# art_limb.net
KiCad netlist of a schematic drawn in EAGLE
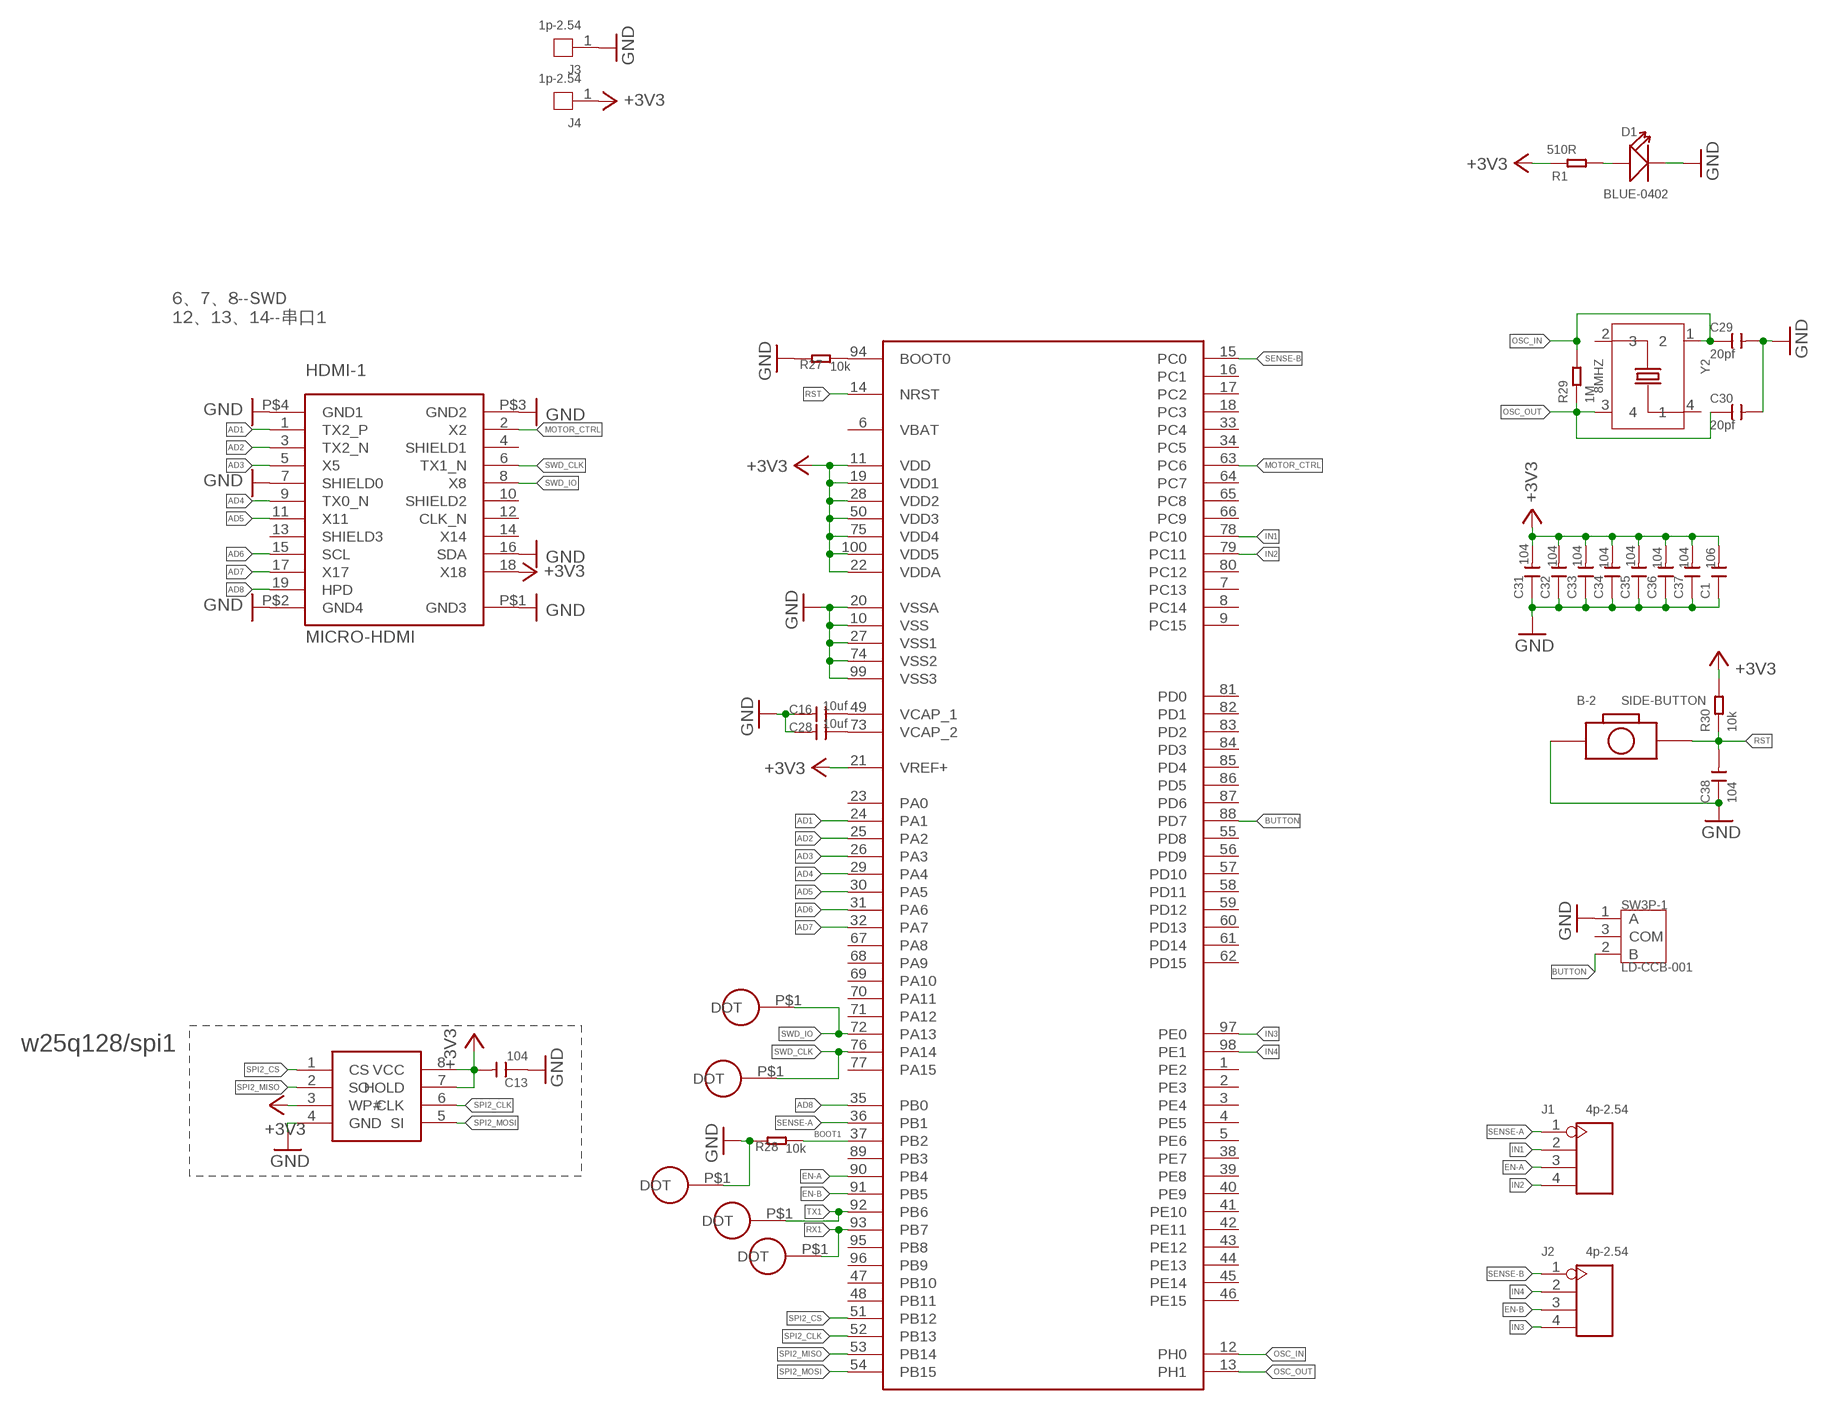
[diagram p0: schematic, sheet 1]

(export (version "E")
  (design (tool "Eeschema 10.0.6"))
  (components
    (comp (ref "B-2")
      (value "SIDE-BUTTON")
      (footprint "eagle-import:SIDE-BUTTON")
      (libsource (lib "eagle-import") (part "SIDE-BUTTON"))
    )
    (comp (ref "C1")
      (value "106")
      (footprint "eagle-import:C0402")
      (fields (field (name "MPN") "GRM1555C1H150JA01D"))
      (libsource (lib "eagle-import") (part "CAP-(0402)"))
    )
    (comp (ref "C13")
      (value "104")
      (footprint "eagle-import:C0402")
      (fields (field (name "MPN") "GRM1555C1H150JA01D"))
      (libsource (lib "eagle-import") (part "CAP-(0402)"))
    )
    (comp (ref "C16")
      (value "10uf")
      (footprint "eagle-import:C0402")
      (fields (field (name "MPN") "GRM1555C1H150JA01D"))
      (libsource (lib "eagle-import") (part "CAP-(0402)"))
    )
    (comp (ref "C28")
      (value "10uf")
      (footprint "eagle-import:C0402")
      (fields (field (name "MPN") "GRM1555C1H150JA01D"))
      (libsource (lib "eagle-import") (part "CAP-(0402)"))
    )
    (comp (ref "C29")
      (value "20pf")
      (footprint "eagle-import:C0402")
      (fields (field (name "MPN") "GRM1555C1H150JA01D"))
      (libsource (lib "eagle-import") (part "CAP-(0402)"))
    )
    (comp (ref "C30")
      (value "20pf")
      (footprint "eagle-import:C0402")
      (fields (field (name "MPN") "GRM1555C1H150JA01D"))
      (libsource (lib "eagle-import") (part "CAP-(0402)"))
    )
    (comp (ref "C31")
      (value "104")
      (footprint "eagle-import:C0402")
      (fields (field (name "MPN") "GRM1555C1H150JA01D"))
      (libsource (lib "eagle-import") (part "CAP-(0402)"))
    )
    (comp (ref "C32")
      (value "104")
      (footprint "eagle-import:C0402")
      (fields (field (name "MPN") "GRM1555C1H150JA01D"))
      (libsource (lib "eagle-import") (part "CAP-(0402)"))
    )
    (comp (ref "C33")
      (value "104")
      (footprint "eagle-import:C0402")
      (fields (field (name "MPN") "GRM1555C1H150JA01D"))
      (libsource (lib "eagle-import") (part "CAP-(0402)"))
    )
    (comp (ref "C34")
      (value "104")
      (footprint "eagle-import:C0402")
      (fields (field (name "MPN") "GRM1555C1H150JA01D"))
      (libsource (lib "eagle-import") (part "CAP-(0402)"))
    )
    (comp (ref "C35")
      (value "104")
      (footprint "eagle-import:C0402")
      (fields (field (name "MPN") "GRM1555C1H150JA01D"))
      (libsource (lib "eagle-import") (part "CAP-(0402)"))
    )
    (comp (ref "C36")
      (value "104")
      (footprint "eagle-import:C0402")
      (fields (field (name "MPN") "GRM1555C1H150JA01D"))
      (libsource (lib "eagle-import") (part "CAP-(0402)"))
    )
    (comp (ref "C37")
      (value "104")
      (footprint "eagle-import:C0402")
      (fields (field (name "MPN") "GRM1555C1H150JA01D"))
      (libsource (lib "eagle-import") (part "CAP-(0402)"))
    )
    (comp (ref "C38")
      (value "104")
      (footprint "eagle-import:C0402")
      (fields (field (name "MPN") "GRM1555C1H150JA01D"))
      (libsource (lib "eagle-import") (part "CAP-(0402)"))
    )
    (comp (ref "D1")
      (value "BLUE-0402")
      (footprint "eagle-import:LED-0402")
      (fields (field (name "MPN") "BL-HB337A-AV-TRB"))
      (libsource (lib "eagle-import") (part "LED-(0402)"))
    )
    (comp (ref "HDMI-1")
      (value "MICRO-HDMI")
      (footprint "eagle-import:HDMI")
      (libsource (lib "eagle-import") (part "MICRO-HDMI"))
    )
    (comp (ref "J1")
      (value "4p-2.54")
      (footprint "eagle-import:H4-2.54")
      (fields (field (name "MPN") "F185-1104A1BSYA1"))
      (libsource (lib "eagle-import") (part "DIP-BLACK-FEMALE-HEADER-VERT(4P-2.54)"))
    )
    (comp (ref "J2")
      (value "4p-2.54")
      (footprint "eagle-import:H4-2.54")
      (fields (field (name "MPN") "F185-1104A1BSYA1"))
      (libsource (lib "eagle-import") (part "DIP-BLACK-FEMALE-HEADER-VERT(4P-2.54)"))
    )
    (comp (ref "J3")
      (value "1p-2.54")
      (footprint "eagle-import:1P-65_35MIL")
      (fields (field (name "MPN") "RF130-1013BBS0741"))
      (libsource (lib "eagle-import") (part "DIP-BLACK-ROUND-FEMALE-HEADER-VERT(1P-2.54)"))
    )
    (comp (ref "J4")
      (value "1p-2.54")
      (footprint "eagle-import:1P-65_35MIL")
      (fields (field (name "MPN") "RF130-1013BBS0741"))
      (libsource (lib "eagle-import") (part "DIP-BLACK-ROUND-FEMALE-HEADER-VERT(1P-2.54)"))
    )
    (comp (ref "R1")
      (value "510R")
      (footprint "eagle-import:R0402")
      (fields (field (name "MPN") "RC0402JR-070RL"))
      (libsource (lib "eagle-import") (part "RES-(0402)"))
    )
    (comp (ref "R27")
      (value "10k")
      (footprint "eagle-import:R0402")
      (fields (field (name "MPN") "RC0402JR-070RL"))
      (libsource (lib "eagle-import") (part "RES-(0402)"))
    )
    (comp (ref "R28")
      (value "10k")
      (footprint "eagle-import:R0402")
      (fields (field (name "MPN") "RC0402JR-070RL"))
      (libsource (lib "eagle-import") (part "RES-(0402)"))
    )
    (comp (ref "R29")
      (value "1M")
      (footprint "eagle-import:R0402")
      (fields (field (name "MPN") "RC0402JR-070RL"))
      (libsource (lib "eagle-import") (part "RES-(0402)"))
    )
    (comp (ref "R30")
      (value "10k")
      (footprint "eagle-import:R0402")
      (fields (field (name "MPN") "RC0402JR-070RL"))
      (libsource (lib "eagle-import") (part "RES-(0402)"))
    )
    (comp (ref "SW3P-1")
      (value "LD-CCB-001")
      (footprint "eagle-import:SW3-2.54-9.0X3.5X3.5+2.0MM")
      (libsource (lib "eagle-import") (part "SWITCH(3P)"))
    )
    (comp (ref "U$1")
      (value "STM32F40XSTM32D40X")
      (footprint "eagle-import:LQFP100")
      (libsource (lib "eagle-import") (part "STM32F40XSTM32D40X"))
    )
    (comp (ref "U$2")
      (value "TEST-POINT")
      (footprint "eagle-import:TEST-POINT")
      (libsource (lib "eagle-import") (part "TEST-POINT"))
    )
    (comp (ref "U$3")
      (value "TEST-POINT")
      (footprint "eagle-import:TEST-POINT")
      (libsource (lib "eagle-import") (part "TEST-POINT"))
    )
    (comp (ref "U$4")
      (value "TEST-POINT")
      (footprint "eagle-import:TEST-POINT")
      (libsource (lib "eagle-import") (part "TEST-POINT"))
    )
    (comp (ref "U$5")
      (value "TEST-POINT")
      (footprint "eagle-import:TEST-POINT")
      (libsource (lib "eagle-import") (part "TEST-POINT"))
    )
    (comp (ref "U$6")
      (value "TEST-POINT")
      (footprint "eagle-import:TEST-POINT")
      (libsource (lib "eagle-import") (part "TEST-POINT"))
    )
    (comp (ref "W25Q128")
      (value "W25Q128")
      (footprint "eagle-import:SOP08")
      (libsource (lib "eagle-import") (part "W25Q128"))
    )
    (comp (ref "Y2")
      (value "8MHZ")
      (footprint "eagle-import:X4-SMD-3.2X2.5X0.7MM")
      (fields (field (name "MPN") "7M-27.120MAAJ-T"))
      (libsource (lib "eagle-import") (part "SMD-CRYSTAL-27.12MHZ-18PF-30PPM-60R(4P-3.2X2.5MM)"))
    )
  )
  (nets
    (net (code "1") (name "+3V3") (class "Default")
      (node (ref "C1") (pin "2") (pinfunction "2_2") (pintype "passive"))
      (node (ref "C13") (pin "2") (pinfunction "2_2") (pintype "passive"))
      (node (ref "C31") (pin "2") (pinfunction "2_2") (pintype "passive"))
      (node (ref "C32") (pin "2") (pinfunction "2_2") (pintype "passive"))
      (node (ref "C33") (pin "2") (pinfunction "2_2") (pintype "passive"))
      (node (ref "C34") (pin "2") (pinfunction "2_2") (pintype "passive"))
      (node (ref "C35") (pin "2") (pinfunction "2_2") (pintype "passive"))
      (node (ref "C36") (pin "2") (pinfunction "2_2") (pintype "passive"))
      (node (ref "C37") (pin "2") (pinfunction "2_2") (pintype "passive"))
      (node (ref "HDMI-1") (pin "18") (pinfunction "X18_18") (pintype "bidirectional"))
      (node (ref "J4") (pin "1") (pinfunction "1_1") (pintype "bidirectional"))
      (node (ref "R1") (pin "2") (pinfunction "2_2") (pintype "passive"))
      (node (ref "R30") (pin "2") (pinfunction "2_2") (pintype "passive"))
      (node (ref "U$1") (pin "100") (pinfunction "VDD5_100") (pintype "bidirectional"))
      (node (ref "U$1") (pin "11") (pinfunction "VDD_11") (pintype "bidirectional"))
      (node (ref "U$1") (pin "19") (pinfunction "VDD1_19") (pintype "bidirectional"))
      (node (ref "U$1") (pin "21") (pinfunction "VREF+_21") (pintype "bidirectional"))
      (node (ref "U$1") (pin "22") (pinfunction "VDDA_22") (pintype "bidirectional"))
      (node (ref "U$1") (pin "28") (pinfunction "VDD2_28") (pintype "bidirectional"))
      (node (ref "U$1") (pin "50") (pinfunction "VDD3_50") (pintype "bidirectional"))
      (node (ref "U$1") (pin "75") (pinfunction "VDD4_75") (pintype "bidirectional"))
      (node (ref "W25Q128") (pin "3") (pinfunction "WP#_3") (pintype "bidirectional"))
      (node (ref "W25Q128") (pin "7") (pinfunction "HOLD_7") (pintype "bidirectional"))
      (node (ref "W25Q128") (pin "8") (pinfunction "VCC_8") (pintype "bidirectional"))
    )
    (net (code "2") (name "/BOOT1") (class "Default")
      (node (ref "R28") (pin "2") (pinfunction "2_2") (pintype "passive"))
      (node (ref "U$1") (pin "37") (pinfunction "PB2_37") (pintype "bidirectional"))
    )
    (net (code "3") (name "AD1") (class "Default")
      (node (ref "HDMI-1") (pin "1") (pinfunction "TX2_P_1") (pintype "bidirectional"))
      (node (ref "U$1") (pin "24") (pinfunction "PA1_24") (pintype "bidirectional"))
    )
    (net (code "4") (name "AD2") (class "Default")
      (node (ref "HDMI-1") (pin "3") (pinfunction "TX2_N_3") (pintype "bidirectional"))
      (node (ref "U$1") (pin "25") (pinfunction "PA2_25") (pintype "bidirectional"))
    )
    (net (code "5") (name "AD3") (class "Default")
      (node (ref "HDMI-1") (pin "5") (pinfunction "X5_5") (pintype "bidirectional"))
      (node (ref "U$1") (pin "26") (pinfunction "PA3_26") (pintype "bidirectional"))
    )
    (net (code "6") (name "AD4") (class "Default")
      (node (ref "HDMI-1") (pin "9") (pinfunction "TX0_N_9") (pintype "bidirectional"))
      (node (ref "U$1") (pin "29") (pinfunction "PA4_29") (pintype "bidirectional"))
    )
    (net (code "7") (name "AD5") (class "Default")
      (node (ref "HDMI-1") (pin "11") (pinfunction "X11_11") (pintype "bidirectional"))
      (node (ref "U$1") (pin "30") (pinfunction "PA5_30") (pintype "bidirectional"))
    )
    (net (code "8") (name "AD6") (class "Default")
      (node (ref "HDMI-1") (pin "15") (pinfunction "SCL_15") (pintype "bidirectional"))
      (node (ref "U$1") (pin "31") (pinfunction "PA6_31") (pintype "bidirectional"))
    )
    (net (code "9") (name "AD7") (class "Default")
      (node (ref "HDMI-1") (pin "17") (pinfunction "X17_17") (pintype "bidirectional"))
      (node (ref "U$1") (pin "32") (pinfunction "PA7_32") (pintype "bidirectional"))
    )
    (net (code "10") (name "AD8") (class "Default")
      (node (ref "HDMI-1") (pin "19") (pinfunction "HPD_19") (pintype "bidirectional"))
      (node (ref "U$1") (pin "35") (pinfunction "PB0_35") (pintype "bidirectional"))
    )
    (net (code "11") (name "BUTTON") (class "Default")
      (node (ref "SW3P-1") (pin "2") (pinfunction "B_2") (pintype "bidirectional"))
      (node (ref "U$1") (pin "88") (pinfunction "PD7_88") (pintype "bidirectional"))
    )
    (net (code "12") (name "EN-A") (class "Default")
      (node (ref "J1") (pin "3") (pinfunction "P$3_3") (pintype "bidirectional"))
      (node (ref "U$1") (pin "90") (pinfunction "PB4_90") (pintype "bidirectional"))
    )
    (net (code "13") (name "EN-B") (class "Default")
      (node (ref "J2") (pin "3") (pinfunction "P$3_3") (pintype "bidirectional"))
      (node (ref "U$1") (pin "91") (pinfunction "PB5_91") (pintype "bidirectional"))
    )
    (net (code "14") (name "GND") (class "Default")
      (node (ref "B-2") (pin "P$2") (pinfunction "1_P$2") (pintype "bidirectional"))
      (node (ref "C1") (pin "1") (pinfunction "1_1") (pintype "passive"))
      (node (ref "C13") (pin "1") (pinfunction "1_1") (pintype "passive"))
      (node (ref "C16") (pin "2") (pinfunction "2_2") (pintype "passive"))
      (node (ref "C28") (pin "2") (pinfunction "2_2") (pintype "passive"))
      (node (ref "C29") (pin "2") (pinfunction "2_2") (pintype "passive"))
      (node (ref "C30") (pin "2") (pinfunction "2_2") (pintype "passive"))
      (node (ref "C31") (pin "1") (pinfunction "1_1") (pintype "passive"))
      (node (ref "C32") (pin "1") (pinfunction "1_1") (pintype "passive"))
      (node (ref "C33") (pin "1") (pinfunction "1_1") (pintype "passive"))
      (node (ref "C34") (pin "1") (pinfunction "1_1") (pintype "passive"))
      (node (ref "C35") (pin "1") (pinfunction "1_1") (pintype "passive"))
      (node (ref "C36") (pin "1") (pinfunction "1_1") (pintype "passive"))
      (node (ref "C37") (pin "1") (pinfunction "1_1") (pintype "passive"))
      (node (ref "C38") (pin "1") (pinfunction "1_1") (pintype "passive"))
      (node (ref "D1") (pin "-") (pinfunction "-_-") (pintype "passive"))
      (node (ref "HDMI-1") (pin "16") (pinfunction "SDA_16") (pintype "bidirectional"))
      (node (ref "HDMI-1") (pin "7") (pinfunction "SHIELD0_7") (pintype "bidirectional"))
      (node (ref "HDMI-1") (pin "P$1") (pinfunction "GND3_P$1") (pintype "bidirectional"))
      (node (ref "HDMI-1") (pin "P$2") (pinfunction "GND4_P$2") (pintype "bidirectional"))
      (node (ref "HDMI-1") (pin "P$3") (pinfunction "GND2_P$3") (pintype "bidirectional"))
      (node (ref "HDMI-1") (pin "P$4") (pinfunction "GND1_P$4") (pintype "bidirectional"))
      (node (ref "J3") (pin "1") (pinfunction "1_1") (pintype "bidirectional"))
      (node (ref "R27") (pin "1") (pinfunction "1_1") (pintype "passive"))
      (node (ref "R28") (pin "1") (pinfunction "1_1") (pintype "passive"))
      (node (ref "SW3P-1") (pin "1") (pinfunction "A_1") (pintype "bidirectional"))
      (node (ref "U$1") (pin "10") (pinfunction "VSS_10") (pintype "bidirectional"))
      (node (ref "U$1") (pin "20") (pinfunction "VSSA_20") (pintype "bidirectional"))
      (node (ref "U$1") (pin "27") (pinfunction "VSS1_27") (pintype "bidirectional"))
      (node (ref "U$1") (pin "74") (pinfunction "VSS2_74") (pintype "bidirectional"))
      (node (ref "U$1") (pin "99") (pinfunction "VSS3_99") (pintype "bidirectional"))
      (node (ref "U$4") (pin "P$1") (pinfunction "DOT_P$1") (pintype "bidirectional"))
      (node (ref "W25Q128") (pin "4") (pinfunction "GND_4") (pintype "bidirectional"))
    )
    (net (code "15") (name "IN1") (class "Default")
      (node (ref "J1") (pin "2") (pinfunction "P$2_2") (pintype "bidirectional"))
      (node (ref "U$1") (pin "78") (pinfunction "PC10_78") (pintype "bidirectional"))
    )
    (net (code "16") (name "IN2") (class "Default")
      (node (ref "J1") (pin "4") (pinfunction "P$4_4") (pintype "bidirectional"))
      (node (ref "U$1") (pin "79") (pinfunction "PC11_79") (pintype "bidirectional"))
    )
    (net (code "17") (name "IN3") (class "Default")
      (node (ref "J2") (pin "4") (pinfunction "P$4_4") (pintype "bidirectional"))
      (node (ref "U$1") (pin "97") (pinfunction "PE0_97") (pintype "bidirectional"))
    )
    (net (code "18") (name "IN4") (class "Default")
      (node (ref "J2") (pin "2") (pinfunction "P$2_2") (pintype "bidirectional"))
      (node (ref "U$1") (pin "98") (pinfunction "PE1_98") (pintype "bidirectional"))
    )
    (net (code "19") (name "MOTOR_CTRL") (class "Default")
      (node (ref "HDMI-1") (pin "2") (pinfunction "X2_2") (pintype "bidirectional"))
      (node (ref "U$1") (pin "63") (pinfunction "PC6_63") (pintype "bidirectional"))
    )
    (net (code "20") (name "Net-(D1-Pad+)") (class "Default")
      (node (ref "D1") (pin "+") (pinfunction "+_+") (pintype "passive"))
      (node (ref "R1") (pin "1") (pinfunction "1_1") (pintype "passive"))
    )
    (net (code "21") (name "Net-(U$1-BOOT0)") (class "Default")
      (node (ref "R27") (pin "2") (pinfunction "2_2") (pintype "passive"))
      (node (ref "U$1") (pin "94") (pinfunction "BOOT0_94") (pintype "bidirectional"))
    )
    (net (code "22") (name "Net-(U$1-VCAP_1)") (class "Default")
      (node (ref "C16") (pin "1") (pinfunction "1_1") (pintype "passive"))
      (node (ref "U$1") (pin "49") (pinfunction "VCAP_1_49") (pintype "bidirectional"))
    )
    (net (code "23") (name "Net-(U$1-VCAP_2)") (class "Default")
      (node (ref "C28") (pin "1") (pinfunction "1_1") (pintype "passive"))
      (node (ref "U$1") (pin "73") (pinfunction "VCAP_2_73") (pintype "bidirectional"))
    )
    (net (code "24") (name "OSC_IN") (class "Default")
      (node (ref "C29") (pin "1") (pinfunction "1_1") (pintype "passive"))
      (node (ref "R29") (pin "2") (pinfunction "2_2") (pintype "passive"))
      (node (ref "U$1") (pin "12") (pinfunction "PH0_12") (pintype "bidirectional"))
      (node (ref "Y2") (pin "1") (pinfunction "2_1") (pintype "bidirectional"))
    )
    (net (code "25") (name "OSC_OUT") (class "Default")
      (node (ref "C30") (pin "1") (pinfunction "1_1") (pintype "passive"))
      (node (ref "R29") (pin "1") (pinfunction "1_1") (pintype "passive"))
      (node (ref "U$1") (pin "13") (pinfunction "PH1_13") (pintype "bidirectional"))
      (node (ref "Y2") (pin "3") (pinfunction "4_3") (pintype "bidirectional"))
    )
    (net (code "26") (name "RST") (class "Default")
      (node (ref "B-2") (pin "P$1") (pinfunction "2_P$1") (pintype "bidirectional"))
      (node (ref "C38") (pin "2") (pinfunction "2_2") (pintype "passive"))
      (node (ref "R30") (pin "1") (pinfunction "1_1") (pintype "passive"))
      (node (ref "U$1") (pin "14") (pinfunction "NRST_14") (pintype "bidirectional"))
    )
    (net (code "27") (name "RX1") (class "Default")
      (node (ref "U$1") (pin "93") (pinfunction "PB7_93") (pintype "bidirectional"))
      (node (ref "U$2") (pin "P$1") (pinfunction "DOT_P$1") (pintype "bidirectional"))
    )
    (net (code "28") (name "SENSE-A") (class "Default")
      (node (ref "J1") (pin "1") (pinfunction "P$1_1") (pintype "bidirectional"))
      (node (ref "U$1") (pin "36") (pinfunction "PB1_36") (pintype "bidirectional"))
    )
    (net (code "29") (name "SENSE-B") (class "Default")
      (node (ref "J2") (pin "1") (pinfunction "P$1_1") (pintype "bidirectional"))
      (node (ref "U$1") (pin "15") (pinfunction "PC0_15") (pintype "bidirectional"))
    )
    (net (code "30") (name "SPI2_CLK") (class "Default")
      (node (ref "U$1") (pin "52") (pinfunction "PB13_52") (pintype "bidirectional"))
      (node (ref "W25Q128") (pin "6") (pinfunction "CLK_6") (pintype "bidirectional"))
    )
    (net (code "31") (name "SPI2_CS") (class "Default")
      (node (ref "U$1") (pin "51") (pinfunction "PB12_51") (pintype "bidirectional"))
      (node (ref "W25Q128") (pin "1") (pinfunction "CS_1") (pintype "bidirectional"))
    )
    (net (code "32") (name "SPI2_MISO") (class "Default")
      (node (ref "U$1") (pin "53") (pinfunction "PB14_53") (pintype "bidirectional"))
      (node (ref "W25Q128") (pin "2") (pinfunction "SO_2") (pintype "bidirectional"))
    )
    (net (code "33") (name "SPI2_MOSI") (class "Default")
      (node (ref "U$1") (pin "54") (pinfunction "PB15_54") (pintype "bidirectional"))
      (node (ref "W25Q128") (pin "5") (pinfunction "SI_5") (pintype "bidirectional"))
    )
    (net (code "34") (name "SWD_CLK") (class "Default")
      (node (ref "HDMI-1") (pin "6") (pinfunction "TX1_N_6") (pintype "bidirectional"))
      (node (ref "U$1") (pin "76") (pinfunction "PA14_76") (pintype "bidirectional"))
      (node (ref "U$6") (pin "P$1") (pinfunction "DOT_P$1") (pintype "bidirectional"))
    )
    (net (code "35") (name "SWD_IO") (class "Default")
      (node (ref "HDMI-1") (pin "8") (pinfunction "X8_8") (pintype "bidirectional"))
      (node (ref "U$1") (pin "72") (pinfunction "PA13_72") (pintype "bidirectional"))
      (node (ref "U$5") (pin "P$1") (pinfunction "DOT_P$1") (pintype "bidirectional"))
    )
    (net (code "36") (name "TX1") (class "Default")
      (node (ref "U$1") (pin "92") (pinfunction "PB6_92") (pintype "bidirectional"))
      (node (ref "U$3") (pin "P$1") (pinfunction "DOT_P$1") (pintype "bidirectional"))
    )
    (net (code "37") (name "unconnected-(HDMI-1-CLK_N-Pad12)") (class "Default")
      (node (ref "HDMI-1") (pin "12") (pinfunction "CLK_N_12") (pintype "bidirectional"))
    )
    (net (code "38") (name "unconnected-(HDMI-1-SHIELD1-Pad4)") (class "Default")
      (node (ref "HDMI-1") (pin "4") (pinfunction "SHIELD1_4") (pintype "bidirectional"))
    )
    (net (code "39") (name "unconnected-(HDMI-1-SHIELD2-Pad10)") (class "Default")
      (node (ref "HDMI-1") (pin "10") (pinfunction "SHIELD2_10") (pintype "bidirectional"))
    )
    (net (code "40") (name "unconnected-(HDMI-1-SHIELD3-Pad13)") (class "Default")
      (node (ref "HDMI-1") (pin "13") (pinfunction "SHIELD3_13") (pintype "bidirectional"))
    )
    (net (code "41") (name "unconnected-(HDMI-1-X14-Pad14)") (class "Default")
      (node (ref "HDMI-1") (pin "14") (pinfunction "X14_14") (pintype "bidirectional"))
    )
    (net (code "42") (name "unconnected-(SW3P-1-COM-Pad3)") (class "Default")
      (node (ref "SW3P-1") (pin "3") (pinfunction "COM_3") (pintype "bidirectional"))
    )
    (net (code "43") (name "unconnected-(U$1-PA0-Pad23)") (class "Default")
      (node (ref "U$1") (pin "23") (pinfunction "PA0_23") (pintype "bidirectional"))
    )
    (net (code "44") (name "unconnected-(U$1-PA8-Pad67)") (class "Default")
      (node (ref "U$1") (pin "67") (pinfunction "PA8_67") (pintype "bidirectional"))
    )
    (net (code "45") (name "unconnected-(U$1-PA9-Pad68)") (class "Default")
      (node (ref "U$1") (pin "68") (pinfunction "PA9_68") (pintype "bidirectional"))
    )
    (net (code "46") (name "unconnected-(U$1-PA10-Pad69)") (class "Default")
      (node (ref "U$1") (pin "69") (pinfunction "PA10_69") (pintype "bidirectional"))
    )
    (net (code "47") (name "unconnected-(U$1-PA11-Pad70)") (class "Default")
      (node (ref "U$1") (pin "70") (pinfunction "PA11_70") (pintype "bidirectional"))
    )
    (net (code "48") (name "unconnected-(U$1-PA12-Pad71)") (class "Default")
      (node (ref "U$1") (pin "71") (pinfunction "PA12_71") (pintype "bidirectional"))
    )
    (net (code "49") (name "unconnected-(U$1-PA15-Pad77)") (class "Default")
      (node (ref "U$1") (pin "77") (pinfunction "PA15_77") (pintype "bidirectional"))
    )
    (net (code "50") (name "unconnected-(U$1-PB3-Pad89)") (class "Default")
      (node (ref "U$1") (pin "89") (pinfunction "PB3_89") (pintype "bidirectional"))
    )
    (net (code "51") (name "unconnected-(U$1-PB8-Pad95)") (class "Default")
      (node (ref "U$1") (pin "95") (pinfunction "PB8_95") (pintype "bidirectional"))
    )
    (net (code "52") (name "unconnected-(U$1-PB9-Pad96)") (class "Default")
      (node (ref "U$1") (pin "96") (pinfunction "PB9_96") (pintype "bidirectional"))
    )
    (net (code "53") (name "unconnected-(U$1-PB10-Pad47)") (class "Default")
      (node (ref "U$1") (pin "47") (pinfunction "PB10_47") (pintype "bidirectional"))
    )
    (net (code "54") (name "unconnected-(U$1-PB11-Pad48)") (class "Default")
      (node (ref "U$1") (pin "48") (pinfunction "PB11_48") (pintype "bidirectional"))
    )
    (net (code "55") (name "unconnected-(U$1-PC1-Pad16)") (class "Default")
      (node (ref "U$1") (pin "16") (pinfunction "PC1_16") (pintype "bidirectional"))
    )
    (net (code "56") (name "unconnected-(U$1-PC2-Pad17)") (class "Default")
      (node (ref "U$1") (pin "17") (pinfunction "PC2_17") (pintype "bidirectional"))
    )
    (net (code "57") (name "unconnected-(U$1-PC3-Pad18)") (class "Default")
      (node (ref "U$1") (pin "18") (pinfunction "PC3_18") (pintype "bidirectional"))
    )
    (net (code "58") (name "unconnected-(U$1-PC4-Pad33)") (class "Default")
      (node (ref "U$1") (pin "33") (pinfunction "PC4_33") (pintype "bidirectional"))
    )
    (net (code "59") (name "unconnected-(U$1-PC5-Pad34)") (class "Default")
      (node (ref "U$1") (pin "34") (pinfunction "PC5_34") (pintype "bidirectional"))
    )
    (net (code "60") (name "unconnected-(U$1-PC7-Pad64)") (class "Default")
      (node (ref "U$1") (pin "64") (pinfunction "PC7_64") (pintype "bidirectional"))
    )
    (net (code "61") (name "unconnected-(U$1-PC8-Pad65)") (class "Default")
      (node (ref "U$1") (pin "65") (pinfunction "PC8_65") (pintype "bidirectional"))
    )
    (net (code "62") (name "unconnected-(U$1-PC9-Pad66)") (class "Default")
      (node (ref "U$1") (pin "66") (pinfunction "PC9_66") (pintype "bidirectional"))
    )
    (net (code "63") (name "unconnected-(U$1-PC12-Pad80)") (class "Default")
      (node (ref "U$1") (pin "80") (pinfunction "PC12_80") (pintype "bidirectional"))
    )
    (net (code "64") (name "unconnected-(U$1-PC13-Pad7)") (class "Default")
      (node (ref "U$1") (pin "7") (pinfunction "PC13_7") (pintype "bidirectional"))
    )
    (net (code "65") (name "unconnected-(U$1-PC14-Pad8)") (class "Default")
      (node (ref "U$1") (pin "8") (pinfunction "PC14_8") (pintype "bidirectional"))
    )
    (net (code "66") (name "unconnected-(U$1-PC15-Pad9)") (class "Default")
      (node (ref "U$1") (pin "9") (pinfunction "PC15_9") (pintype "bidirectional"))
    )
    (net (code "67") (name "unconnected-(U$1-PD0-Pad81)") (class "Default")
      (node (ref "U$1") (pin "81") (pinfunction "PD0_81") (pintype "bidirectional"))
    )
    (net (code "68") (name "unconnected-(U$1-PD1-Pad82)") (class "Default")
      (node (ref "U$1") (pin "82") (pinfunction "PD1_82") (pintype "bidirectional"))
    )
    (net (code "69") (name "unconnected-(U$1-PD2-Pad83)") (class "Default")
      (node (ref "U$1") (pin "83") (pinfunction "PD2_83") (pintype "bidirectional"))
    )
    (net (code "70") (name "unconnected-(U$1-PD3-Pad84)") (class "Default")
      (node (ref "U$1") (pin "84") (pinfunction "PD3_84") (pintype "bidirectional"))
    )
    (net (code "71") (name "unconnected-(U$1-PD4-Pad85)") (class "Default")
      (node (ref "U$1") (pin "85") (pinfunction "PD4_85") (pintype "bidirectional"))
    )
    (net (code "72") (name "unconnected-(U$1-PD5-Pad86)") (class "Default")
      (node (ref "U$1") (pin "86") (pinfunction "PD5_86") (pintype "bidirectional"))
    )
    (net (code "73") (name "unconnected-(U$1-PD6-Pad87)") (class "Default")
      (node (ref "U$1") (pin "87") (pinfunction "PD6_87") (pintype "bidirectional"))
    )
    (net (code "74") (name "unconnected-(U$1-PD8-Pad55)") (class "Default")
      (node (ref "U$1") (pin "55") (pinfunction "PD8_55") (pintype "bidirectional"))
    )
    (net (code "75") (name "unconnected-(U$1-PD9-Pad56)") (class "Default")
      (node (ref "U$1") (pin "56") (pinfunction "PD9_56") (pintype "bidirectional"))
    )
    (net (code "76") (name "unconnected-(U$1-PD10-Pad57)") (class "Default")
      (node (ref "U$1") (pin "57") (pinfunction "PD10_57") (pintype "bidirectional"))
    )
    (net (code "77") (name "unconnected-(U$1-PD11-Pad58)") (class "Default")
      (node (ref "U$1") (pin "58") (pinfunction "PD11_58") (pintype "bidirectional"))
    )
    (net (code "78") (name "unconnected-(U$1-PD12-Pad59)") (class "Default")
      (node (ref "U$1") (pin "59") (pinfunction "PD12_59") (pintype "bidirectional"))
    )
    (net (code "79") (name "unconnected-(U$1-PD13-Pad60)") (class "Default")
      (node (ref "U$1") (pin "60") (pinfunction "PD13_60") (pintype "bidirectional"))
    )
    (net (code "80") (name "unconnected-(U$1-PD14-Pad61)") (class "Default")
      (node (ref "U$1") (pin "61") (pinfunction "PD14_61") (pintype "bidirectional"))
    )
    (net (code "81") (name "unconnected-(U$1-PD15-Pad62)") (class "Default")
      (node (ref "U$1") (pin "62") (pinfunction "PD15_62") (pintype "bidirectional"))
    )
    (net (code "82") (name "unconnected-(U$1-PE2-Pad1)") (class "Default")
      (node (ref "U$1") (pin "1") (pinfunction "PE2_1") (pintype "bidirectional"))
    )
    (net (code "83") (name "unconnected-(U$1-PE3-Pad2)") (class "Default")
      (node (ref "U$1") (pin "2") (pinfunction "PE3_2") (pintype "bidirectional"))
    )
    (net (code "84") (name "unconnected-(U$1-PE4-Pad3)") (class "Default")
      (node (ref "U$1") (pin "3") (pinfunction "PE4_3") (pintype "bidirectional"))
    )
    (net (code "85") (name "unconnected-(U$1-PE5-Pad4)") (class "Default")
      (node (ref "U$1") (pin "4") (pinfunction "PE5_4") (pintype "bidirectional"))
    )
    (net (code "86") (name "unconnected-(U$1-PE6-Pad5)") (class "Default")
      (node (ref "U$1") (pin "5") (pinfunction "PE6_5") (pintype "bidirectional"))
    )
    (net (code "87") (name "unconnected-(U$1-PE7-Pad38)") (class "Default")
      (node (ref "U$1") (pin "38") (pinfunction "PE7_38") (pintype "bidirectional"))
    )
    (net (code "88") (name "unconnected-(U$1-PE8-Pad39)") (class "Default")
      (node (ref "U$1") (pin "39") (pinfunction "PE8_39") (pintype "bidirectional"))
    )
    (net (code "89") (name "unconnected-(U$1-PE9-Pad40)") (class "Default")
      (node (ref "U$1") (pin "40") (pinfunction "PE9_40") (pintype "bidirectional"))
    )
    (net (code "90") (name "unconnected-(U$1-PE10-Pad41)") (class "Default")
      (node (ref "U$1") (pin "41") (pinfunction "PE10_41") (pintype "bidirectional"))
    )
    (net (code "91") (name "unconnected-(U$1-PE11-Pad42)") (class "Default")
      (node (ref "U$1") (pin "42") (pinfunction "PE11_42") (pintype "bidirectional"))
    )
    (net (code "92") (name "unconnected-(U$1-PE12-Pad43)") (class "Default")
      (node (ref "U$1") (pin "43") (pinfunction "PE12_43") (pintype "bidirectional"))
    )
    (net (code "93") (name "unconnected-(U$1-PE13-Pad44)") (class "Default")
      (node (ref "U$1") (pin "44") (pinfunction "PE13_44") (pintype "bidirectional"))
    )
    (net (code "94") (name "unconnected-(U$1-PE14-Pad45)") (class "Default")
      (node (ref "U$1") (pin "45") (pinfunction "PE14_45") (pintype "bidirectional"))
    )
    (net (code "95") (name "unconnected-(U$1-PE15-Pad46)") (class "Default")
      (node (ref "U$1") (pin "46") (pinfunction "PE15_46") (pintype "bidirectional"))
    )
    (net (code "96") (name "unconnected-(U$1-VBAT-Pad6)") (class "Default")
      (node (ref "U$1") (pin "6") (pinfunction "VBAT_6") (pintype "bidirectional"))
    )
    (net (code "97") (name "unconnected-(Y2-1-Pad4)") (class "Default")
      (node (ref "Y2") (pin "4") (pinfunction "1_4") (pintype "bidirectional"))
    )
    (net (code "98") (name "unconnected-(Y2-3-Pad2)") (class "Default")
      (node (ref "Y2") (pin "2") (pinfunction "3_2") (pintype "bidirectional"))
    )
  )
)
